# TopSheet.net
KiCad netlist of a schematic drawn in Altium Designer
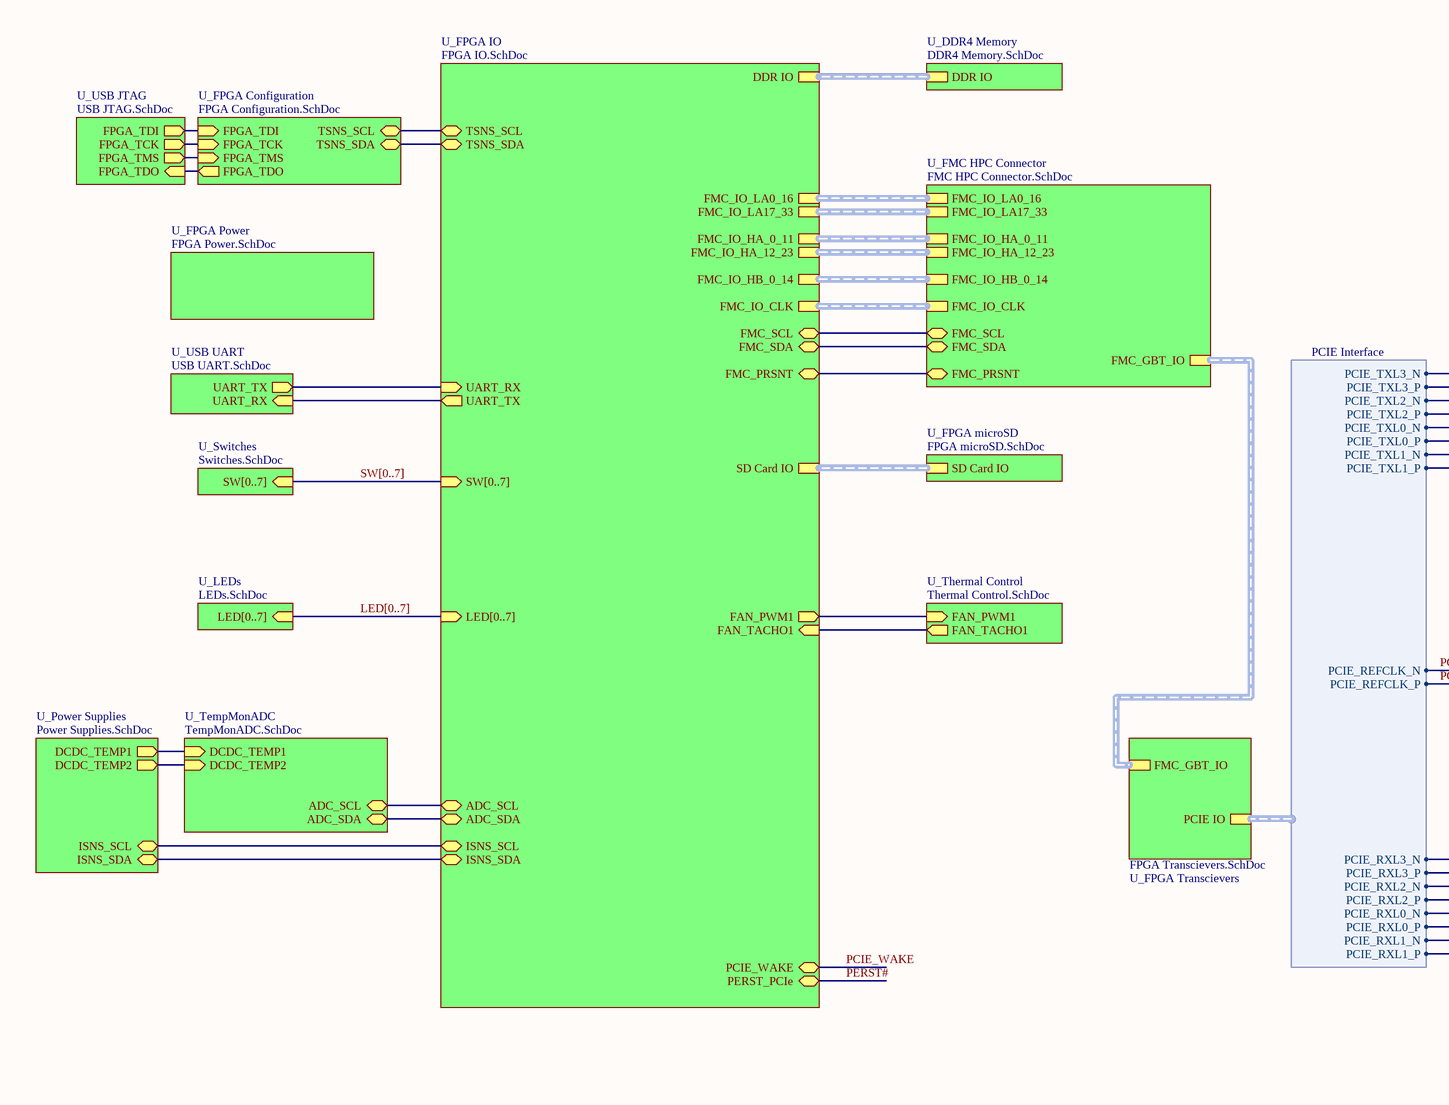
[diagram p0: TopSheet.SchDoc, left]
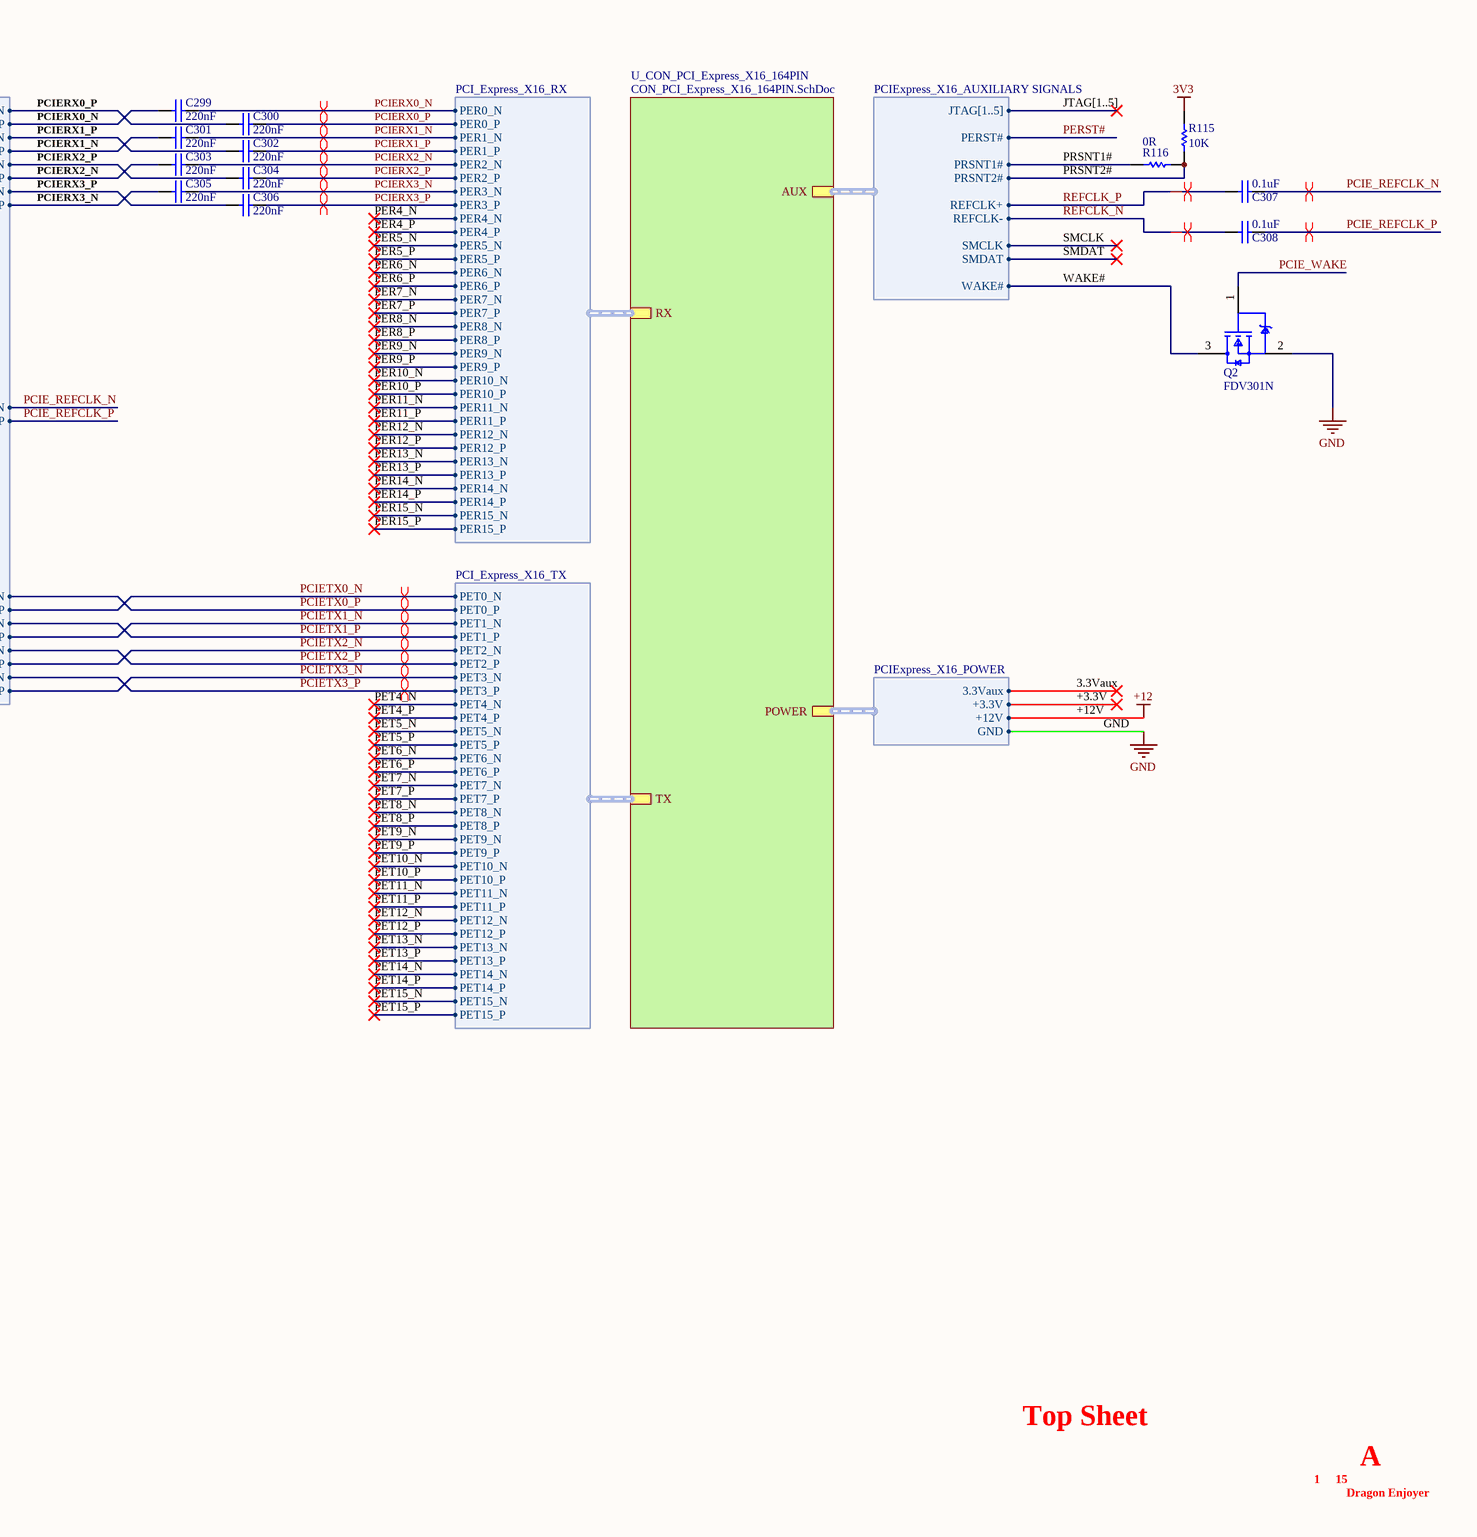
[diagram p1: TopSheet.SchDoc, right]

(export (version "E")
  (design (tool "Eeschema 10.0.6"))
  (components
    (comp (ref "C299")
      (value "220nF")
      (footprint "CAPC1005X56X25LL10T15")
      (fields
        (field (name "MANUFACTURER") "AVX Interconnect / Elco")
        (field (name "PART NUMBER") "04026D224MAT2A")
      )
      (libsource (lib "Altium Content Vault") (part "CAP"))
    )
    (comp (ref "C300")
      (value "220nF")
      (footprint "CAPC1005X56X25LL10T15")
      (fields
        (field (name "MANUFACTURER") "AVX Interconnect / Elco")
        (field (name "PART NUMBER") "04026D224MAT2A")
      )
      (libsource (lib "Altium Content Vault") (part "CAP"))
    )
    (comp (ref "C301")
      (value "220nF")
      (footprint "CAPC1005X56X25LL10T15")
      (fields
        (field (name "MANUFACTURER") "AVX Interconnect / Elco")
        (field (name "PART NUMBER") "04026D224MAT2A")
      )
      (libsource (lib "Altium Content Vault") (part "CAP"))
    )
    (comp (ref "C302")
      (value "220nF")
      (footprint "CAPC1005X56X25LL10T15")
      (fields
        (field (name "MANUFACTURER") "AVX Interconnect / Elco")
        (field (name "PART NUMBER") "04026D224MAT2A")
      )
      (libsource (lib "Altium Content Vault") (part "CAP"))
    )
    (comp (ref "C303")
      (value "220nF")
      (footprint "CAPC1005X56X25LL10T15")
      (fields
        (field (name "MANUFACTURER") "AVX Interconnect / Elco")
        (field (name "PART NUMBER") "04026D224MAT2A")
      )
      (libsource (lib "Altium Content Vault") (part "CAP"))
    )
    (comp (ref "C304")
      (value "220nF")
      (footprint "CAPC1005X56X25LL10T15")
      (fields
        (field (name "MANUFACTURER") "AVX Interconnect / Elco")
        (field (name "PART NUMBER") "04026D224MAT2A")
      )
      (libsource (lib "Altium Content Vault") (part "CAP"))
    )
    (comp (ref "C305")
      (value "220nF")
      (footprint "CAPC1005X56X25LL10T15")
      (fields
        (field (name "MANUFACTURER") "AVX Interconnect / Elco")
        (field (name "PART NUMBER") "04026D224MAT2A")
      )
      (libsource (lib "Altium Content Vault") (part "CAP"))
    )
    (comp (ref "C306")
      (value "220nF")
      (footprint "CAPC1005X56X25LL10T15")
      (fields
        (field (name "MANUFACTURER") "AVX Interconnect / Elco")
        (field (name "PART NUMBER") "04026D224MAT2A")
      )
      (libsource (lib "Altium Content Vault") (part "CAP"))
    )
    (comp (ref "C307")
      (value "0.1uF")
      (footprint "CAPC1005X56X25LL10T15")
      (fields
        (field (name "MANUFACTURER") "AVX Interconnect / Elco")
        (field (name "PART NUMBER") "04026D104KAT2A")
      )
      (libsource (lib "Altium Content Vault") (part "CAP"))
    )
    (comp (ref "C308")
      (value "0.1uF")
      (footprint "CAPC1005X56X25LL10T15")
      (fields
        (field (name "MANUFACTURER") "AVX Interconnect / Elco")
        (field (name "PART NUMBER") "04026D104KAT2A")
      )
      (libsource (lib "Altium Content Vault") (part "CAP"))
    )
    (comp (ref "Q2")
      (value "FDV301N")
      (footprint "FP-318-08-MFG")
      (description "MOSFET N-CH 25V 220MA SOT-23")
      (fields
        (field (name "MANUFACTURER") "ON Semiconductor")
        (field (name "OCTOPART") "https://octopart.com/fdv301n-on+semiconductor-84326713")
      )
      (libsource (lib "Altium Content Vault") (part "4b65c62267dd4506eaef0021093ec31"))
    )
    (comp (ref "R115")
      (value "10K")
      (footprint "RESC1609X50X30NL8T20")
      (description "Chip Resistor, 10 KOhm, +/- 1%, 100 mW, -55 to 155 degC, 0603 (1608 Metric), RoHS, Tape and Reel")
      (fields
        (field (name "MANUFACTURER") "Vishay Semiconductor")
        (field (name "Comment") "CRCW060310K0FKEA")
      )
      (libsource (lib "Altium Content Vault") (part "RES-2"))
    )
    (comp (ref "R116")
      (value "0R")
      (footprint "RESC1005X40X25ML05T10")
      (fields (field (name "PART NUMBER") "CRCW04020000Z0EDHP") (field (name "MANUFACTURER") "Vishay Dale"))
      (libsource (lib "Altium Content Vault") (part "RES"))
    )
  )
  (nets
    (net (code "51") (name "/PCIERX0_N") (class "Default")
      (node (ref "C299") (pin "2") (pinfunction "2_2") (pintype "passive"))
    )
    (net (code "52") (name "/PCIERX0_P") (class "Default")
      (node (ref "C300") (pin "2") (pinfunction "2_2") (pintype "passive"))
    )
    (net (code "53") (name "/PCIERX1_N") (class "Default")
      (node (ref "C301") (pin "2") (pinfunction "2_2") (pintype "passive"))
    )
    (net (code "54") (name "/PCIERX1_P") (class "Default")
      (node (ref "C302") (pin "2") (pinfunction "2_2") (pintype "passive"))
    )
    (net (code "55") (name "/PCIERX2_N") (class "Default")
      (node (ref "C303") (pin "2") (pinfunction "2_2") (pintype "passive"))
    )
    (net (code "56") (name "/PCIERX2_P") (class "Default")
      (node (ref "C304") (pin "2") (pinfunction "2_2") (pintype "passive"))
    )
    (net (code "57") (name "/PCIERX3_N") (class "Default")
      (node (ref "C305") (pin "2") (pinfunction "2_2") (pintype "passive"))
    )
    (net (code "58") (name "/PCIERX3_P") (class "Default")
      (node (ref "C306") (pin "2") (pinfunction "2_2") (pintype "passive"))
    )
    (net (code "67") (name "/PCIE_REFCLK_N") (class "Default")
      (node (ref "C307") (pin "2") (pinfunction "2_2") (pintype "passive"))
    )
    (net (code "68") (name "/PCIE_REFCLK_P") (class "Default")
      (node (ref "C308") (pin "2") (pinfunction "2_2") (pintype "passive"))
    )
    (net (code "69") (name "/PCIE_TXL0_N") (class "Default")
      (node (ref "C304") (pin "1") (pinfunction "1_1") (pintype "passive"))
    )
    (net (code "70") (name "/PCIE_TXL0_P") (class "Default")
      (node (ref "C303") (pin "1") (pinfunction "1_1") (pintype "passive"))
    )
    (net (code "71") (name "/PCIE_TXL1_N") (class "Default")
      (node (ref "C306") (pin "1") (pinfunction "1_1") (pintype "passive"))
    )
    (net (code "72") (name "/PCIE_TXL1_P") (class "Default")
      (node (ref "C305") (pin "1") (pinfunction "1_1") (pintype "passive"))
    )
    (net (code "73") (name "/PCIE_TXL2_N") (class "Default")
      (node (ref "C302") (pin "1") (pinfunction "1_1") (pintype "passive"))
    )
    (net (code "74") (name "/PCIE_TXL2_P") (class "Default")
      (node (ref "C301") (pin "1") (pinfunction "1_1") (pintype "passive"))
    )
    (net (code "75") (name "/PCIE_TXL3_N") (class "Default")
      (node (ref "C300") (pin "1") (pinfunction "1_1") (pintype "passive"))
    )
    (net (code "76") (name "/PCIE_TXL3_P") (class "Default")
      (node (ref "C299") (pin "1") (pinfunction "1_1") (pintype "passive"))
    )
    (net (code "77") (name "/PCIE_WAKE") (class "Default")
      (node (ref "Q2") (pin "1") (pinfunction "G_1") (pintype "passive"))
    )
    (net (code "127") (name "/PRSNT1#") (class "Default")
      (node (ref "R116") (pin "1") (pinfunction "1_1") (pintype "passive"))
    )
    (net (code "128") (name "/PRSNT2#") (class "Default")
      (node (ref "R115") (pin "1") (pinfunction "1_1") (pintype "passive"))
      (node (ref "R116") (pin "2") (pinfunction "2_2") (pintype "passive"))
    )
    (net (code "129") (name "/REFCLK_N") (class "Default")
      (node (ref "C308") (pin "1") (pinfunction "1_1") (pintype "passive"))
    )
    (net (code "130") (name "/REFCLK_P") (class "Default")
      (node (ref "C307") (pin "1") (pinfunction "1_1") (pintype "passive"))
    )
    (net (code "139") (name "/WAKE#") (class "Default")
      (node (ref "Q2") (pin "3") (pinfunction "D_3") (pintype "passive"))
    )
    (net (code "145") (name "3V3") (class "Default")
      (node (ref "R115") (pin "2") (pinfunction "2_2") (pintype "passive"))
    )
    (net (code "146") (name "GND") (class "Default")
      (node (ref "Q2") (pin "2") (pinfunction "S_2") (pintype "passive"))
    )
  )
)
